# peltier_regulator.net
KiCad netlist of a schematic drawn in EAGLE
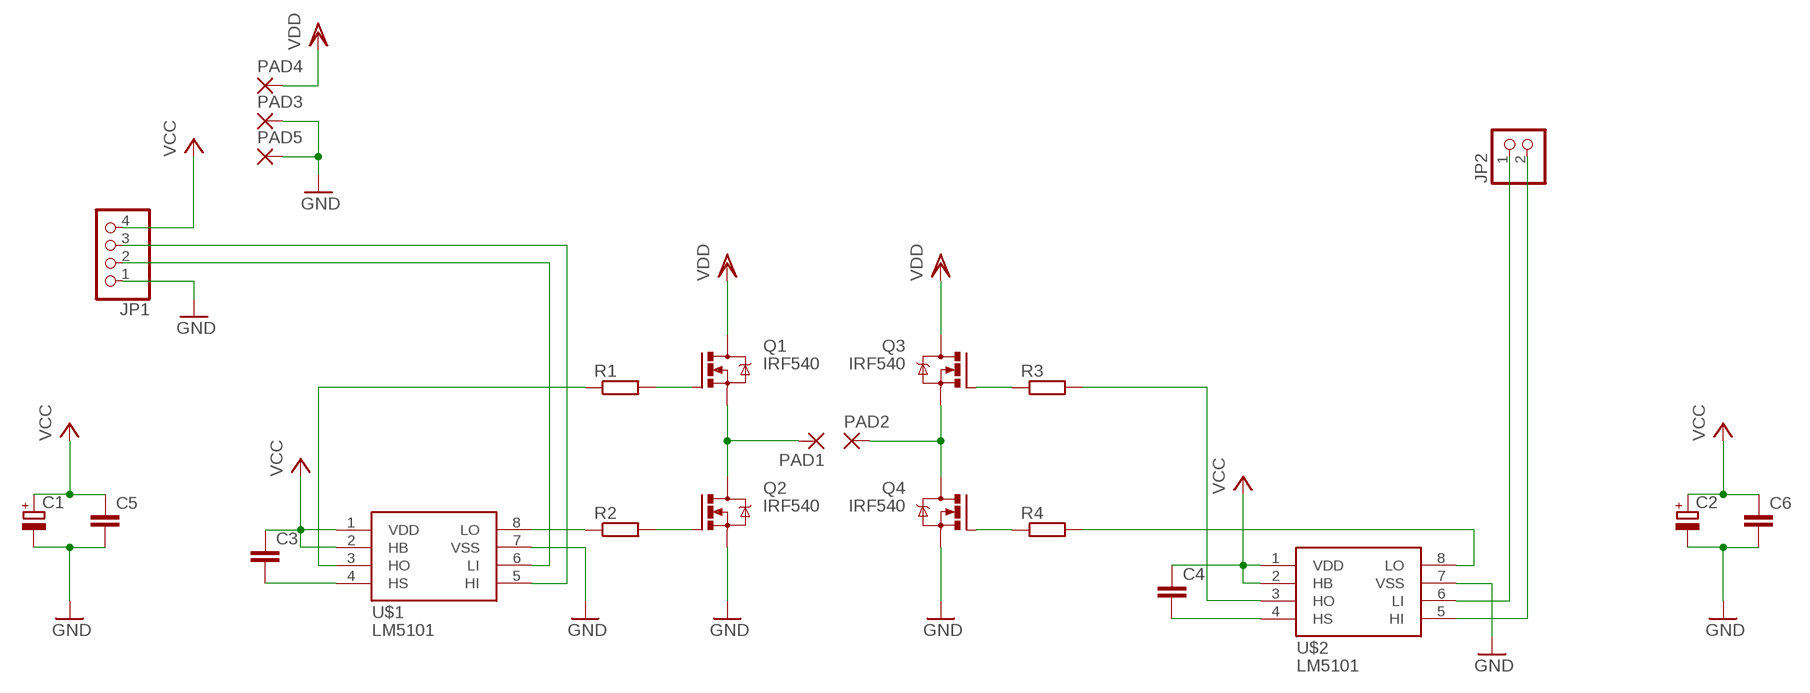
[diagram p0: schematic, sheet 1]

(export (version "E")
  (design (tool "Eeschema 10.0.6"))
  (components
    (comp (ref "C1")
      (value "CPOL-EUD")
      (footprint "eagle-import:PANASONIC_D")
      (libsource (lib "eagle-import") (part "CPOL-EUD"))
    )
    (comp (ref "C2")
      (value "CPOL-EUD")
      (footprint "eagle-import:PANASONIC_D")
      (libsource (lib "eagle-import") (part "CPOL-EUD"))
    )
    (comp (ref "C3")
      (value "C-EUC1206")
      (footprint "eagle-import:C1206")
      (libsource (lib "eagle-import") (part "C-EUC1206"))
    )
    (comp (ref "C4")
      (value "C-EUC1206")
      (footprint "eagle-import:C1206")
      (libsource (lib "eagle-import") (part "C-EUC1206"))
    )
    (comp (ref "C5")
      (value "C-EUC1206")
      (footprint "eagle-import:C1206")
      (libsource (lib "eagle-import") (part "C-EUC1206"))
    )
    (comp (ref "C6")
      (value "C-EUC1206")
      (footprint "eagle-import:C1206")
      (libsource (lib "eagle-import") (part "C-EUC1206"))
    )
    (comp (ref "JP1")
      (value "PINHD-1X4")
      (footprint "eagle-import:1X04")
      (libsource (lib "eagle-import") (part "PINHD-1X4"))
    )
    (comp (ref "JP2")
      (value "PINHD-1X2")
      (footprint "eagle-import:1X02")
      (libsource (lib "eagle-import") (part "PINHD-1X2"))
    )
    (comp (ref "PAD1")
      (value "2,54/1,0")
      (footprint "eagle-import:2,54_1,0")
      (libsource (lib "eagle-import") (part "2,54/1,0"))
    )
    (comp (ref "PAD2")
      (value "2,54/1,0")
      (footprint "eagle-import:2,54_1,0")
      (libsource (lib "eagle-import") (part "2,54/1,0"))
    )
    (comp (ref "PAD3")
      (value "2,54/1,0")
      (footprint "eagle-import:2,54_1,0")
      (libsource (lib "eagle-import") (part "2,54/1,0"))
    )
    (comp (ref "PAD4")
      (value "2,54/1,0")
      (footprint "eagle-import:2,54_1,0")
      (libsource (lib "eagle-import") (part "2,54/1,0"))
    )
    (comp (ref "PAD5")
      (value "2,54/1,0")
      (footprint "eagle-import:2,54_1,0")
      (libsource (lib "eagle-import") (part "2,54/1,0"))
    )
    (comp (ref "Q1")
      (value "IRF540")
      (footprint "eagle-import:TO220BV")
      (libsource (lib "eagle-import") (part "IRF540"))
    )
    (comp (ref "Q2")
      (value "IRF540")
      (footprint "eagle-import:TO220BV")
      (libsource (lib "eagle-import") (part "IRF540"))
    )
    (comp (ref "Q3")
      (value "IRF540")
      (footprint "eagle-import:TO220BV")
      (libsource (lib "eagle-import") (part "IRF540"))
    )
    (comp (ref "Q4")
      (value "IRF540")
      (footprint "eagle-import:TO220BV")
      (libsource (lib "eagle-import") (part "IRF540"))
    )
    (comp (ref "R1")
      (value "R-EU_R1206")
      (footprint "eagle-import:R1206")
      (libsource (lib "eagle-import") (part "R-EU_R1206"))
    )
    (comp (ref "R2")
      (value "R-EU_R1206")
      (footprint "eagle-import:R1206")
      (libsource (lib "eagle-import") (part "R-EU_R1206"))
    )
    (comp (ref "R3")
      (value "R-EU_R1206")
      (footprint "eagle-import:R1206")
      (libsource (lib "eagle-import") (part "R-EU_R1206"))
    )
    (comp (ref "R4")
      (value "R-EU_R1206")
      (footprint "eagle-import:R1206")
      (libsource (lib "eagle-import") (part "R-EU_R1206"))
    )
    (comp (ref "U$1")
      (value "LM5101")
      (footprint "eagle-import:SOIC8")
      (libsource (lib "eagle-import") (part "LM5101"))
    )
    (comp (ref "U$2")
      (value "LM5101")
      (footprint "eagle-import:SOIC8")
      (libsource (lib "eagle-import") (part "LM5101"))
    )
  )
  (nets
    (net (code "1") (name "GND") (class "Default")
      (node (ref "C1") (pin "-") (pinfunction "-_-") (pintype "passive"))
      (node (ref "C2") (pin "-") (pinfunction "-_-") (pintype "passive"))
      (node (ref "C5") (pin "2") (pinfunction "2_2") (pintype "passive"))
      (node (ref "C6") (pin "2") (pinfunction "2_2") (pintype "passive"))
      (node (ref "JP1") (pin "1") (pinfunction "1_1") (pintype "passive"))
      (node (ref "PAD3") (pin "1") (pinfunction "P_1") (pintype "passive"))
      (node (ref "PAD5") (pin "1") (pinfunction "P_1") (pintype "passive"))
      (node (ref "Q2") (pin "S") (pinfunction "S_S") (pintype "passive"))
      (node (ref "Q4") (pin "S") (pinfunction "S_S") (pintype "passive"))
      (node (ref "U$1") (pin "7") (pinfunction "VSS_7") (pintype "bidirectional"))
      (node (ref "U$2") (pin "7") (pinfunction "VSS_7") (pintype "bidirectional"))
    )
    (net (code "2") (name "Net-(PAD1-P)") (class "Default")
      (node (ref "PAD1") (pin "1") (pinfunction "P_1") (pintype "passive"))
      (node (ref "Q1") (pin "S") (pinfunction "S_S") (pintype "passive"))
      (node (ref "Q2") (pin "D") (pinfunction "D_D") (pintype "passive"))
    )
    (net (code "3") (name "Net-(PAD2-P)") (class "Default")
      (node (ref "PAD2") (pin "1") (pinfunction "P_1") (pintype "passive"))
      (node (ref "Q3") (pin "S") (pinfunction "S_S") (pintype "passive"))
      (node (ref "Q4") (pin "D") (pinfunction "D_D") (pintype "passive"))
    )
    (net (code "4") (name "Net-(Q1-PadG)") (class "Default")
      (node (ref "Q1") (pin "G") (pinfunction "G_G") (pintype "passive"))
      (node (ref "R1") (pin "2") (pinfunction "2_2") (pintype "passive"))
    )
    (net (code "5") (name "Net-(Q2-PadG)") (class "Default")
      (node (ref "Q2") (pin "G") (pinfunction "G_G") (pintype "passive"))
      (node (ref "R2") (pin "2") (pinfunction "2_2") (pintype "passive"))
    )
    (net (code "6") (name "Net-(Q3-PadG)") (class "Default")
      (node (ref "Q3") (pin "G") (pinfunction "G_G") (pintype "passive"))
      (node (ref "R3") (pin "1") (pinfunction "1_1") (pintype "passive"))
    )
    (net (code "7") (name "Net-(Q4-PadG)") (class "Default")
      (node (ref "Q4") (pin "G") (pinfunction "G_G") (pintype "passive"))
      (node (ref "R4") (pin "1") (pinfunction "1_1") (pintype "passive"))
    )
    (net (code "8") (name "Net-(U$1-HI)") (class "Default")
      (node (ref "JP1") (pin "3") (pinfunction "3_3") (pintype "passive"))
      (node (ref "U$1") (pin "5") (pinfunction "HI_5") (pintype "bidirectional"))
    )
    (net (code "9") (name "Net-(U$1-HO)") (class "Default")
      (node (ref "R1") (pin "1") (pinfunction "1_1") (pintype "passive"))
      (node (ref "U$1") (pin "3") (pinfunction "HO_3") (pintype "bidirectional"))
    )
    (net (code "10") (name "Net-(U$1-HS)") (class "Default")
      (node (ref "C3") (pin "2") (pinfunction "2_2") (pintype "passive"))
      (node (ref "U$1") (pin "4") (pinfunction "HS_4") (pintype "bidirectional"))
    )
    (net (code "11") (name "Net-(U$1-LI)") (class "Default")
      (node (ref "JP1") (pin "2") (pinfunction "2_2") (pintype "passive"))
      (node (ref "U$1") (pin "6") (pinfunction "LI_6") (pintype "bidirectional"))
    )
    (net (code "12") (name "Net-(U$1-LO)") (class "Default")
      (node (ref "R2") (pin "1") (pinfunction "1_1") (pintype "passive"))
      (node (ref "U$1") (pin "8") (pinfunction "LO_8") (pintype "bidirectional"))
    )
    (net (code "13") (name "Net-(U$2-HI)") (class "Default")
      (node (ref "JP2") (pin "2") (pinfunction "2_2") (pintype "passive"))
      (node (ref "U$2") (pin "5") (pinfunction "HI_5") (pintype "bidirectional"))
    )
    (net (code "14") (name "Net-(U$2-HO)") (class "Default")
      (node (ref "R3") (pin "2") (pinfunction "2_2") (pintype "passive"))
      (node (ref "U$2") (pin "3") (pinfunction "HO_3") (pintype "bidirectional"))
    )
    (net (code "15") (name "Net-(U$2-HS)") (class "Default")
      (node (ref "C4") (pin "2") (pinfunction "2_2") (pintype "passive"))
      (node (ref "U$2") (pin "4") (pinfunction "HS_4") (pintype "bidirectional"))
    )
    (net (code "16") (name "Net-(U$2-LI)") (class "Default")
      (node (ref "JP2") (pin "1") (pinfunction "1_1") (pintype "passive"))
      (node (ref "U$2") (pin "6") (pinfunction "LI_6") (pintype "bidirectional"))
    )
    (net (code "17") (name "Net-(U$2-LO)") (class "Default")
      (node (ref "R4") (pin "2") (pinfunction "2_2") (pintype "passive"))
      (node (ref "U$2") (pin "8") (pinfunction "LO_8") (pintype "bidirectional"))
    )
    (net (code "18") (name "VCC") (class "Default")
      (node (ref "C1") (pin "+") (pinfunction "+_+") (pintype "passive"))
      (node (ref "C2") (pin "+") (pinfunction "+_+") (pintype "passive"))
      (node (ref "C3") (pin "1") (pinfunction "1_1") (pintype "passive"))
      (node (ref "C4") (pin "1") (pinfunction "1_1") (pintype "passive"))
      (node (ref "C5") (pin "1") (pinfunction "1_1") (pintype "passive"))
      (node (ref "C6") (pin "1") (pinfunction "1_1") (pintype "passive"))
      (node (ref "JP1") (pin "4") (pinfunction "4_4") (pintype "passive"))
      (node (ref "U$1") (pin "1") (pinfunction "VDD_1") (pintype "bidirectional"))
      (node (ref "U$1") (pin "2") (pinfunction "HB_2") (pintype "bidirectional"))
      (node (ref "U$2") (pin "1") (pinfunction "VDD_1") (pintype "bidirectional"))
      (node (ref "U$2") (pin "2") (pinfunction "HB_2") (pintype "bidirectional"))
    )
    (net (code "19") (name "VDD") (class "Default")
      (node (ref "PAD4") (pin "1") (pinfunction "P_1") (pintype "passive"))
      (node (ref "Q1") (pin "D") (pinfunction "D_D") (pintype "passive"))
      (node (ref "Q3") (pin "D") (pinfunction "D_D") (pintype "passive"))
    )
  )
)
